# ESP32_AC_dimmer_10ch_r2.net
KiCad netlist of a schematic drawn in EAGLE
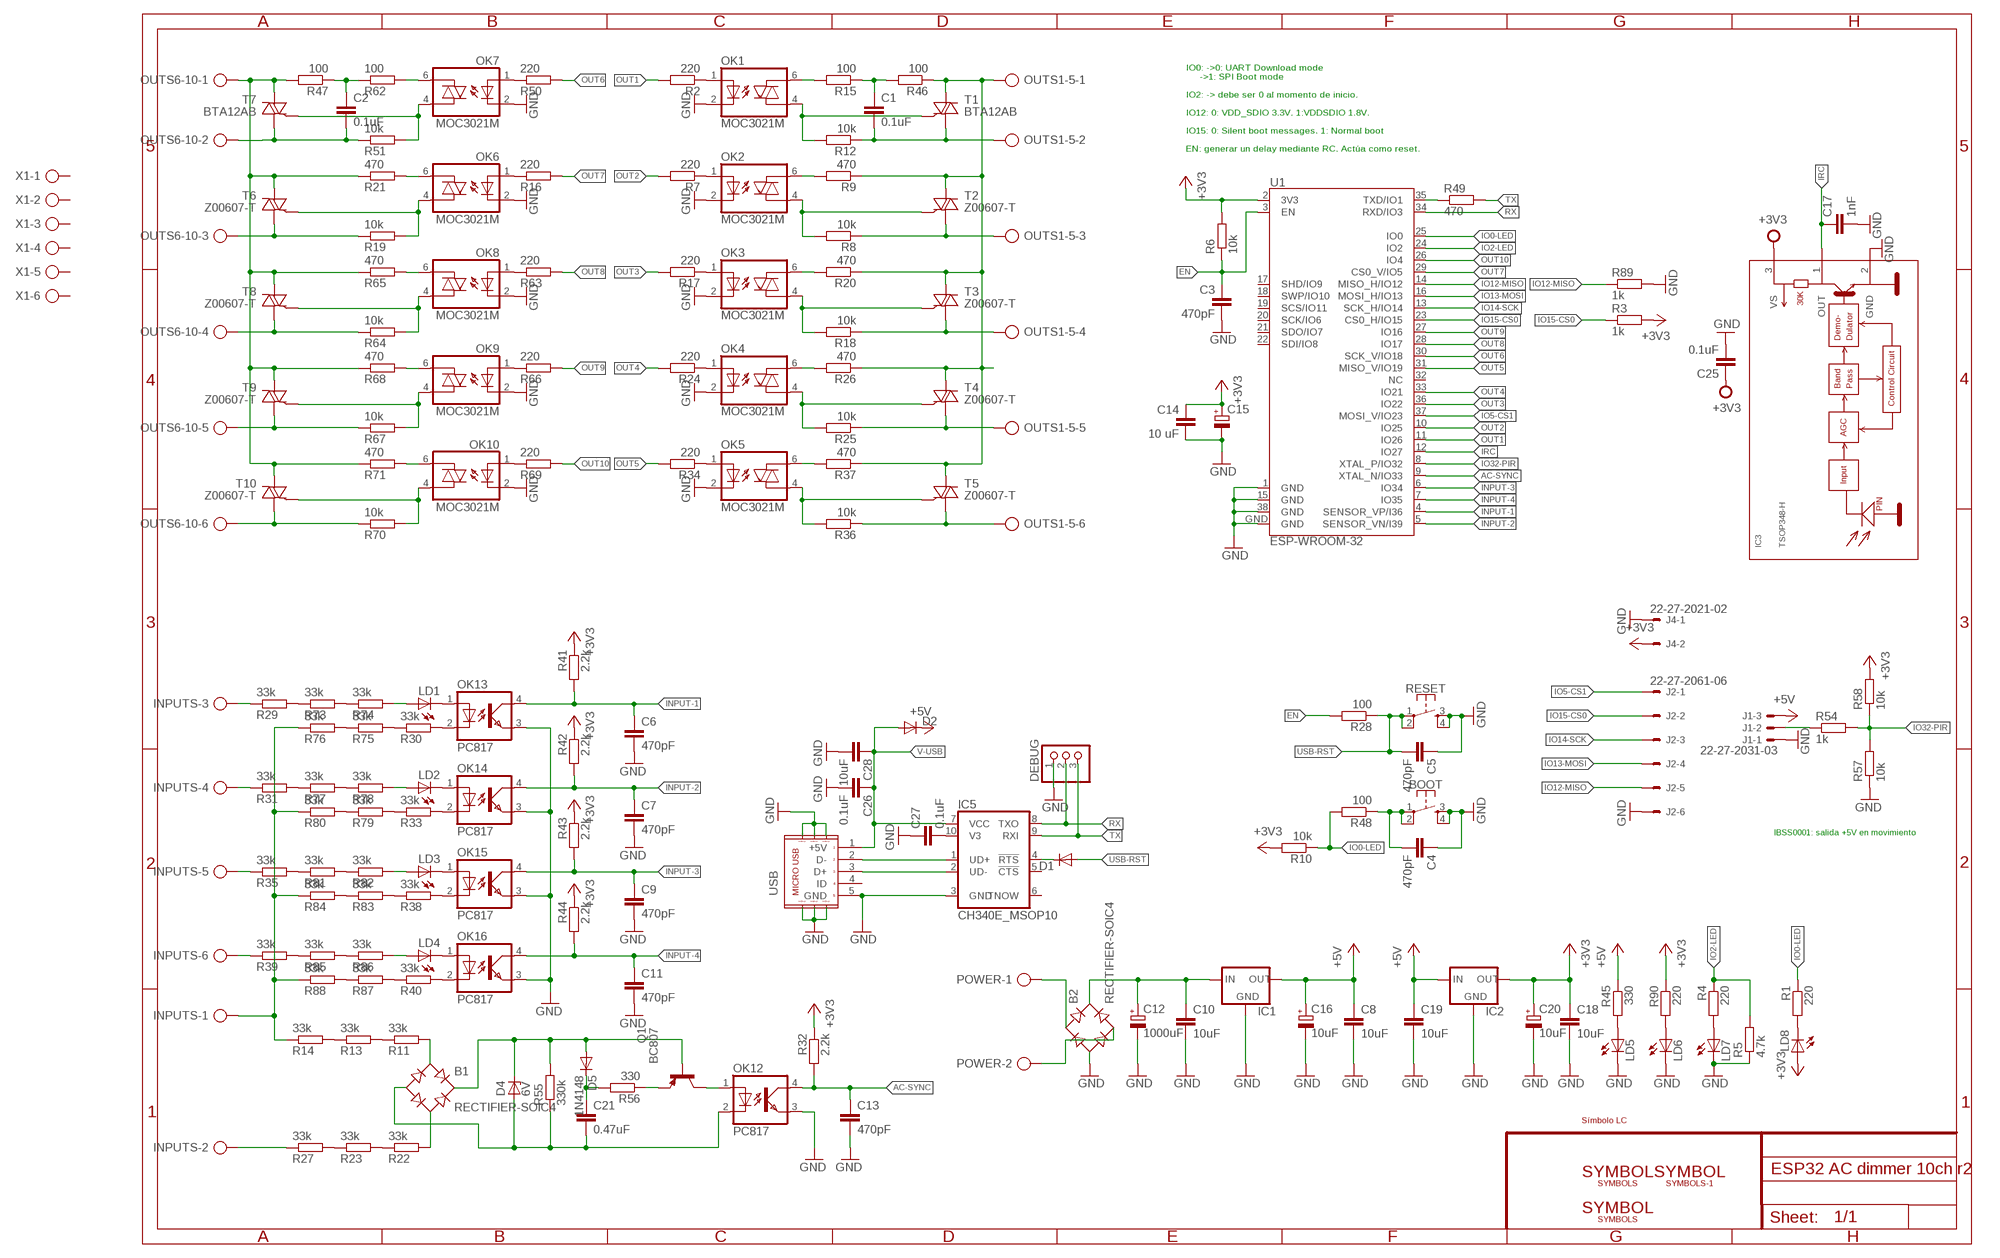
[diagram p0: schematic, sheet 1]

(export (version "E")
  (design (tool "Eeschema 10.0.6"))
  (components
    (comp (ref "B1")
      (value "RECTIFIER-SOIC4")
      (footprint "eagle-import:SOIC4")
      (libsource (lib "eagle-import") (part "RECTIFIER-SOIC4"))
    )
    (comp (ref "B2")
      (value "RECTIFIER-SOIC4")
      (footprint "eagle-import:SOIC4")
      (libsource (lib "eagle-import") (part "RECTIFIER-SOIC4"))
    )
    (comp (ref "BOOT")
      (value "MOMENTARY-SWITCH-SPST-2-SMD-4.6X2.8MM")
      (footprint "eagle-import:TACTILE_SWITCH_SMD_4.6X2.8MM")
      (libsource (lib "eagle-import") (part "MOMENTARY-SWITCH-SPST-2-SMD-4.6X2.8MM"))
    )
    (comp (ref "C1")
      (value "0.1uF")
      (footprint "eagle-import:C075-042X103")
      (libsource (lib "eagle-import") (part "C-EU075-042X103"))
    )
    (comp (ref "C2")
      (value "0.1uF")
      (footprint "eagle-import:C075-042X103")
      (libsource (lib "eagle-import") (part "C-EU075-042X103"))
    )
    (comp (ref "C3")
      (value "470pF")
      (footprint "eagle-import:C0603")
      (libsource (lib "eagle-import") (part "C-EUC0603"))
    )
    (comp (ref "C4")
      (value "470pF")
      (footprint "eagle-import:C0603")
      (libsource (lib "eagle-import") (part "C-EUC0603"))
    )
    (comp (ref "C5")
      (value "470pF")
      (footprint "eagle-import:C0603")
      (libsource (lib "eagle-import") (part "C-EUC0603"))
    )
    (comp (ref "C6")
      (value "470pF")
      (footprint "eagle-import:C0603")
      (libsource (lib "eagle-import") (part "C-EUC0603"))
    )
    (comp (ref "C7")
      (value "470pF")
      (footprint "eagle-import:C0603")
      (libsource (lib "eagle-import") (part "C-EUC0603"))
    )
    (comp (ref "C8")
      (value "10uF")
      (footprint "eagle-import:C0805")
      (libsource (lib "eagle-import") (part "C-EUC0805"))
    )
    (comp (ref "C9")
      (value "470pF")
      (footprint "eagle-import:C0603")
      (libsource (lib "eagle-import") (part "C-EUC0603"))
    )
    (comp (ref "C10")
      (value "10uF")
      (footprint "eagle-import:C0805")
      (libsource (lib "eagle-import") (part "C-EUC0805"))
    )
    (comp (ref "C11")
      (value "470pF")
      (footprint "eagle-import:C0603")
      (libsource (lib "eagle-import") (part "C-EUC0603"))
    )
    (comp (ref "C12")
      (value "1000uF")
      (footprint "eagle-import:E3,5-8")
      (libsource (lib "eagle-import") (part "CPOL-EUE3.5-8"))
    )
    (comp (ref "C13")
      (value "470pF")
      (footprint "eagle-import:C0603")
      (libsource (lib "eagle-import") (part "C-EUC0603"))
    )
    (comp (ref "C14")
      (value "10 uF")
      (footprint "eagle-import:C0805")
      (libsource (lib "eagle-import") (part "C-EUC0805"))
    )
    (comp (ref "C15")
      (value "CPOL-EUSMCA")
      (footprint "eagle-import:SMC_A")
      (libsource (lib "eagle-import") (part "rcl_334_CPOL-EUSMCA"))
    )
    (comp (ref "C16")
      (value "10uF")
      (footprint "eagle-import:SMC_A")
      (libsource (lib "eagle-import") (part "rcl_334_CPOL-EUSMCA"))
    )
    (comp (ref "C17")
      (value "1nF")
      (footprint "eagle-import:C0603")
      (libsource (lib "eagle-import") (part "C-EUC0603"))
    )
    (comp (ref "C18")
      (value "10uF")
      (footprint "eagle-import:C0805")
      (libsource (lib "eagle-import") (part "C-EUC0805"))
    )
    (comp (ref "C19")
      (value "10uF")
      (footprint "eagle-import:C0805")
      (libsource (lib "eagle-import") (part "C-EUC0805"))
    )
    (comp (ref "C20")
      (value "10uF")
      (footprint "eagle-import:SMC_A")
      (libsource (lib "eagle-import") (part "rcl_334_CPOL-EUSMCA"))
    )
    (comp (ref "C21")
      (value "0.47uF")
      (footprint "eagle-import:C0805")
      (libsource (lib "eagle-import") (part "C-EUC0805"))
    )
    (comp (ref "C25")
      (value "0.1uF")
      (footprint "eagle-import:C0603")
      (libsource (lib "eagle-import") (part "C-EUC0603"))
    )
    (comp (ref "C26")
      (value "0.1uF")
      (footprint "eagle-import:C0603")
      (libsource (lib "eagle-import") (part "C-EUC0603"))
    )
    (comp (ref "C27")
      (value "0.1uF")
      (footprint "eagle-import:C0603")
      (libsource (lib "eagle-import") (part "C-EUC0603"))
    )
    (comp (ref "C28")
      (value "10uF")
      (footprint "eagle-import:RCL_C0805")
      (libsource (lib "eagle-import") (part "RCL_C-EUC0805"))
    )
    (comp (ref "D1")
      (value "DIODE-SOD323-R")
      (footprint "eagle-import:SOD323-R")
      (libsource (lib "eagle-import") (part "DIODE-SOD323-R"))
    )
    (comp (ref "D2")
      (value "DIODE-SOD323-R")
      (footprint "eagle-import:SOD323-R")
      (libsource (lib "eagle-import") (part "DIODE-SOD323-R"))
    )
    (comp (ref "D4")
      (value "6V")
      (footprint "eagle-import:SOD80C")
      (libsource (lib "eagle-import") (part "ZENER-DIODESOD80C"))
    )
    (comp (ref "D5")
      (value "1N4148")
      (footprint "eagle-import:MINIMELF")
      (libsource (lib "eagle-import") (part "DIODE-MINIMELF"))
    )
    (comp (ref "DEBUG")
      (value "PINHD-1X3")
      (footprint "eagle-import:1X03")
      (libsource (lib "eagle-import") (part "PINHD-1X3"))
    )
    (comp (ref "IC1")
      (value "LM1117")
      (footprint "eagle-import:SOT223")
      (libsource (lib "eagle-import") (part "LM1117"))
    )
    (comp (ref "IC2")
      (value "LM1117")
      (footprint "eagle-import:SOT223")
      (libsource (lib "eagle-import") (part "LM1117"))
    )
    (comp (ref "IC3")
      (value "TSOP348-H")
      (footprint "eagle-import:TSOP348H")
      (libsource (lib "eagle-import") (part "TSOP348-H"))
    )
    (comp (ref "IC5")
      (value "CH340E_MSOP10")
      (footprint "eagle-import:MSOP10")
      (libsource (lib "eagle-import") (part "CH340E_MSOP10"))
    )
    (comp (ref "INPUTS")
      (value "AK500/6")
      (footprint "eagle-import:AK500_6")
      (libsource (lib "eagle-import") (part "AK500/6"))
    )
    (comp (ref "J1")
      (value "22-27-2031-03")
      (footprint "eagle-import:6410-03")
      (libsource (lib "eagle-import") (part "22-?-0327-2031"))
    )
    (comp (ref "J2")
      (value "22-27-2061-06")
      (footprint "eagle-import:6410-06")
      (fields (field (name "MF") "MOLEX"))
      (libsource (lib "eagle-import") (part "22-?-0627-2061"))
    )
    (comp (ref "J4")
      (value "22-27-2021-02")
      (footprint "eagle-import:6410-02")
      (fields (field (name "MF") "MOLEX"))
      (libsource (lib "eagle-import") (part "22-?-0227-2021"))
    )
    (comp (ref "LD1")
      (value "LEDCHIPLED_0805")
      (footprint "eagle-import:CHIPLED_0805")
      (libsource (lib "eagle-import") (part "LEDCHIPLED_0805"))
    )
    (comp (ref "LD2")
      (value "LEDCHIPLED_0805")
      (footprint "eagle-import:CHIPLED_0805")
      (libsource (lib "eagle-import") (part "LEDCHIPLED_0805"))
    )
    (comp (ref "LD3")
      (value "LEDCHIPLED_0805")
      (footprint "eagle-import:CHIPLED_0805")
      (libsource (lib "eagle-import") (part "LEDCHIPLED_0805"))
    )
    (comp (ref "LD4")
      (value "LEDCHIPLED_0805")
      (footprint "eagle-import:CHIPLED_0805")
      (libsource (lib "eagle-import") (part "LEDCHIPLED_0805"))
    )
    (comp (ref "LD5")
      (value "LEDCHIPLED_0805")
      (footprint "eagle-import:CHIPLED_0805")
      (fields (field (name "SPICEPREFIX") "L"))
      (libsource (lib "eagle-import") (part "LEDCHIPLED_0805"))
    )
    (comp (ref "LD6")
      (value "LEDCHIPLED_0805")
      (footprint "eagle-import:CHIPLED_0805")
      (fields (field (name "SPICEPREFIX") "L"))
      (libsource (lib "eagle-import") (part "LEDCHIPLED_0805"))
    )
    (comp (ref "LD7")
      (value "LEDCHIPLED_0805")
      (footprint "eagle-import:CHIPLED_0805")
      (fields (field (name "SPICEPREFIX") "L"))
      (libsource (lib "eagle-import") (part "LEDCHIPLED_0805"))
    )
    (comp (ref "LD8")
      (value "LEDCHIPLED_0805")
      (footprint "eagle-import:CHIPLED_0805")
      (fields (field (name "SPICEPREFIX") "L"))
      (libsource (lib "eagle-import") (part "LEDCHIPLED_0805"))
    )
    (comp (ref "OK1")
      (value "MOC3021M")
      (footprint "eagle-import:DIL06")
      (libsource (lib "eagle-import") (part "MOC30M21"))
    )
    (comp (ref "OK2")
      (value "MOC3021M")
      (footprint "eagle-import:DIL06")
      (libsource (lib "eagle-import") (part "MOC30M21"))
    )
    (comp (ref "OK3")
      (value "MOC3021M")
      (footprint "eagle-import:DIL06")
      (libsource (lib "eagle-import") (part "MOC30M21"))
    )
    (comp (ref "OK4")
      (value "MOC3021M")
      (footprint "eagle-import:DIL06")
      (libsource (lib "eagle-import") (part "MOC30M21"))
    )
    (comp (ref "OK5")
      (value "MOC3021M")
      (footprint "eagle-import:DIL06")
      (libsource (lib "eagle-import") (part "MOC30M21"))
    )
    (comp (ref "OK6")
      (value "MOC3021M")
      (footprint "eagle-import:DIL06")
      (libsource (lib "eagle-import") (part "MOC30M21"))
    )
    (comp (ref "OK7")
      (value "MOC3021M")
      (footprint "eagle-import:DIL06")
      (libsource (lib "eagle-import") (part "MOC30M21"))
    )
    (comp (ref "OK8")
      (value "MOC3021M")
      (footprint "eagle-import:DIL06")
      (libsource (lib "eagle-import") (part "MOC30M21"))
    )
    (comp (ref "OK9")
      (value "MOC3021M")
      (footprint "eagle-import:DIL06")
      (libsource (lib "eagle-import") (part "MOC30M21"))
    )
    (comp (ref "OK10")
      (value "MOC3021M")
      (footprint "eagle-import:DIL06")
      (libsource (lib "eagle-import") (part "MOC30M21"))
    )
    (comp (ref "OK12")
      (value "PC817")
      (footprint "eagle-import:DIL04")
      (libsource (lib "eagle-import") (part "PC817"))
    )
    (comp (ref "OK13")
      (value "PC817")
      (footprint "eagle-import:DIL04")
      (libsource (lib "eagle-import") (part "PC817"))
    )
    (comp (ref "OK14")
      (value "PC817")
      (footprint "eagle-import:DIL04")
      (libsource (lib "eagle-import") (part "PC817"))
    )
    (comp (ref "OK15")
      (value "PC817")
      (footprint "eagle-import:DIL04")
      (libsource (lib "eagle-import") (part "PC817"))
    )
    (comp (ref "OK16")
      (value "PC817")
      (footprint "eagle-import:DIL04")
      (libsource (lib "eagle-import") (part "PC817"))
    )
    (comp (ref "OUTS1-5")
      (value "AK500/6")
      (footprint "eagle-import:AK500_6")
      (libsource (lib "eagle-import") (part "AK500/6"))
    )
    (comp (ref "OUTS6-10")
      (value "AK500/6")
      (footprint "eagle-import:AK500_6")
      (libsource (lib "eagle-import") (part "AK500/6"))
    )
    (comp (ref "POWER")
      (value "AK500/2")
      (footprint "eagle-import:AK500_2")
      (libsource (lib "eagle-import") (part "AK500/2"))
    )
    (comp (ref "Q1")
      (value "BC807")
      (footprint "eagle-import:SOT23-BEC")
      (libsource (lib "eagle-import") (part "-PNP-SOT23-BECBC807-25"))
    )
    (comp (ref "R1")
      (value "220")
      (footprint "eagle-import:R0603")
      (fields (field (name "SPICEPREFIX") "R"))
      (libsource (lib "eagle-import") (part "R-EU_R0603"))
    )
    (comp (ref "R2")
      (value "220")
      (footprint "eagle-import:R0603")
      (libsource (lib "eagle-import") (part "R-EU_R0603"))
    )
    (comp (ref "R3")
      (value "1k")
      (footprint "eagle-import:R0603")
      (libsource (lib "eagle-import") (part "R-EU_R0603"))
    )
    (comp (ref "R4")
      (value "220")
      (footprint "eagle-import:R0603")
      (fields (field (name "SPICEPREFIX") "R"))
      (libsource (lib "eagle-import") (part "R-EU_R0603"))
    )
    (comp (ref "R5")
      (value "4.7k")
      (footprint "eagle-import:R0603")
      (libsource (lib "eagle-import") (part "R-EU_R0603"))
    )
    (comp (ref "R6")
      (value "10k")
      (footprint "eagle-import:R0603")
      (libsource (lib "eagle-import") (part "R-EU_R0603"))
    )
    (comp (ref "R7")
      (value "220")
      (footprint "eagle-import:R0603")
      (libsource (lib "eagle-import") (part "R-EU_R0603"))
    )
    (comp (ref "R8")
      (value "10k")
      (footprint "eagle-import:0204_5")
      (libsource (lib "eagle-import") (part "R-EU_0204/5"))
    )
    (comp (ref "R9")
      (value "470")
      (footprint "eagle-import:0204_5")
      (libsource (lib "eagle-import") (part "R-EU_0204/5"))
    )
    (comp (ref "R10")
      (value "10k")
      (footprint "eagle-import:R0603")
      (libsource (lib "eagle-import") (part "R-EU_R0603"))
    )
    (comp (ref "R11")
      (value "33k")
      (footprint "eagle-import:R0805")
      (libsource (lib "eagle-import") (part "R-EU_R0805"))
    )
    (comp (ref "R12")
      (value "10k")
      (footprint "eagle-import:0204_5")
      (libsource (lib "eagle-import") (part "R-EU_0204/5"))
    )
    (comp (ref "R13")
      (value "33k")
      (footprint "eagle-import:R0805")
      (libsource (lib "eagle-import") (part "R-EU_R0805"))
    )
    (comp (ref "R14")
      (value "33k")
      (footprint "eagle-import:R0805")
      (libsource (lib "eagle-import") (part "R-EU_R0805"))
    )
    (comp (ref "R15")
      (value "100")
      (footprint "eagle-import:0204_5")
      (libsource (lib "eagle-import") (part "R-EU_0204/5"))
    )
    (comp (ref "R16")
      (value "220")
      (footprint "eagle-import:R0603")
      (libsource (lib "eagle-import") (part "R-EU_R0603"))
    )
    (comp (ref "R17")
      (value "220")
      (footprint "eagle-import:R0603")
      (libsource (lib "eagle-import") (part "R-EU_R0603"))
    )
    (comp (ref "R18")
      (value "10k")
      (footprint "eagle-import:0204_5")
      (libsource (lib "eagle-import") (part "R-EU_0204/5"))
    )
    (comp (ref "R19")
      (value "10k")
      (footprint "eagle-import:0204_5")
      (libsource (lib "eagle-import") (part "R-EU_0204/5"))
    )
    (comp (ref "R20")
      (value "470")
      (footprint "eagle-import:0204_5")
      (libsource (lib "eagle-import") (part "R-EU_0204/5"))
    )
    (comp (ref "R21")
      (value "470")
      (footprint "eagle-import:0204_5")
      (libsource (lib "eagle-import") (part "R-EU_0204/5"))
    )
    (comp (ref "R22")
      (value "33k")
      (footprint "eagle-import:R0805")
      (libsource (lib "eagle-import") (part "R-EU_R0805"))
    )
    (comp (ref "R23")
      (value "33k")
      (footprint "eagle-import:R0805")
      (libsource (lib "eagle-import") (part "R-EU_R0805"))
    )
    (comp (ref "R24")
      (value "220")
      (footprint "eagle-import:R0603")
      (libsource (lib "eagle-import") (part "R-EU_R0603"))
    )
    (comp (ref "R25")
      (value "10k")
      (footprint "eagle-import:0204_5")
      (libsource (lib "eagle-import") (part "R-EU_0204/5"))
    )
    (comp (ref "R26")
      (value "470")
      (footprint "eagle-import:0204_5")
      (libsource (lib "eagle-import") (part "R-EU_0204/5"))
    )
    (comp (ref "R27")
      (value "33k")
      (footprint "eagle-import:R0805")
      (libsource (lib "eagle-import") (part "R-EU_R0805"))
    )
    (comp (ref "R28")
      (value "100")
      (footprint "eagle-import:R0603")
      (libsource (lib "eagle-import") (part "R-EU_R0603"))
    )
    (comp (ref "R29")
      (value "33k")
      (footprint "eagle-import:R0805")
      (libsource (lib "eagle-import") (part "R-EU_R0805"))
    )
    (comp (ref "R30")
      (value "33k")
      (footprint "eagle-import:R0805")
      (libsource (lib "eagle-import") (part "R-EU_R0805"))
    )
    (comp (ref "R31")
      (value "33k")
      (footprint "eagle-import:R0805")
      (libsource (lib "eagle-import") (part "R-EU_R0805"))
    )
    (comp (ref "R32")
      (value "2.2k")
      (footprint "eagle-import:R0603")
      (libsource (lib "eagle-import") (part "R-EU_R0603"))
    )
    (comp (ref "R33")
      (value "33k")
      (footprint "eagle-import:R0805")
      (libsource (lib "eagle-import") (part "R-EU_R0805"))
    )
    (comp (ref "R34")
      (value "220")
      (footprint "eagle-import:R0603")
      (libsource (lib "eagle-import") (part "R-EU_R0603"))
    )
    (comp (ref "R35")
      (value "33k")
      (footprint "eagle-import:R0805")
      (libsource (lib "eagle-import") (part "R-EU_R0805"))
    )
    (comp (ref "R36")
      (value "10k")
      (footprint "eagle-import:0204_5")
      (libsource (lib "eagle-import") (part "R-EU_0204/5"))
    )
    (comp (ref "R37")
      (value "470")
      (footprint "eagle-import:0204_5")
      (libsource (lib "eagle-import") (part "R-EU_0204/5"))
    )
    (comp (ref "R38")
      (value "33k")
      (footprint "eagle-import:R0805")
      (libsource (lib "eagle-import") (part "R-EU_R0805"))
    )
    (comp (ref "R39")
      (value "33k")
      (footprint "eagle-import:R0805")
      (libsource (lib "eagle-import") (part "R-EU_R0805"))
    )
    (comp (ref "R40")
      (value "33k")
      (footprint "eagle-import:R0805")
      (libsource (lib "eagle-import") (part "R-EU_R0805"))
    )
    (comp (ref "R41")
      (value "2.2k")
      (footprint "eagle-import:R0603")
      (libsource (lib "eagle-import") (part "R-EU_R0603"))
    )
    (comp (ref "R42")
      (value "2.2k")
      (footprint "eagle-import:R0603")
      (libsource (lib "eagle-import") (part "R-EU_R0603"))
    )
    (comp (ref "R43")
      (value "2.2k")
      (footprint "eagle-import:R0603")
      (libsource (lib "eagle-import") (part "R-EU_R0603"))
    )
    (comp (ref "R44")
      (value "2.2k")
      (footprint "eagle-import:R0603")
      (libsource (lib "eagle-import") (part "R-EU_R0603"))
    )
    (comp (ref "R45")
      (value "330")
      (footprint "eagle-import:R0603")
      (fields (field (name "SPICEPREFIX") "R"))
      (libsource (lib "eagle-import") (part "R-EU_R0603"))
    )
    (comp (ref "R46")
      (value "100")
      (footprint "eagle-import:0204_7")
      (libsource (lib "eagle-import") (part "R-EU_0204/7"))
    )
    (comp (ref "R47")
      (value "100")
      (footprint "eagle-import:0204_7")
      (libsource (lib "eagle-import") (part "R-EU_0204/7"))
    )
    (comp (ref "R48")
      (value "100")
      (footprint "eagle-import:R0603")
      (libsource (lib "eagle-import") (part "R-EU_R0603"))
    )
    (comp (ref "R49")
      (value "470")
      (footprint "eagle-import:R0603")
      (libsource (lib "eagle-import") (part "R-EU_R0603"))
    )
    (comp (ref "R50")
      (value "220")
      (footprint "eagle-import:R0603")
      (libsource (lib "eagle-import") (part "R-EU_R0603"))
    )
    (comp (ref "R51")
      (value "10k")
      (footprint "eagle-import:0204_5")
      (libsource (lib "eagle-import") (part "R-EU_0204/5"))
    )
    (comp (ref "R54")
      (value "1k")
      (footprint "eagle-import:R0603")
      (libsource (lib "eagle-import") (part "R-EU_R0603"))
    )
    (comp (ref "R55")
      (value "330k")
      (footprint "eagle-import:R0805")
      (libsource (lib "eagle-import") (part "R-EU_R0805"))
    )
    (comp (ref "R56")
      (value "330")
      (footprint "eagle-import:R0805")
      (libsource (lib "eagle-import") (part "R-EU_R0805"))
    )
    (comp (ref "R57")
      (value "10k")
      (footprint "eagle-import:R0603")
      (libsource (lib "eagle-import") (part "R-EU_R0603"))
    )
    (comp (ref "R58")
      (value "10k")
      (footprint "eagle-import:R0603")
      (libsource (lib "eagle-import") (part "R-EU_R0603"))
    )
    (comp (ref "R62")
      (value "100")
      (footprint "eagle-import:0204_5")
      (libsource (lib "eagle-import") (part "R-EU_0204/5"))
    )
    (comp (ref "R63")
      (value "220")
      (footprint "eagle-import:R0603")
      (libsource (lib "eagle-import") (part "R-EU_R0603"))
    )
    (comp (ref "R64")
      (value "10k")
      (footprint "eagle-import:0204_5")
      (libsource (lib "eagle-import") (part "R-EU_0204/5"))
    )
    (comp (ref "R65")
      (value "470")
      (footprint "eagle-import:0204_5")
      (libsource (lib "eagle-import") (part "R-EU_0204/5"))
    )
    (comp (ref "R66")
      (value "220")
      (footprint "eagle-import:R0603")
      (libsource (lib "eagle-import") (part "R-EU_R0603"))
    )
    (comp (ref "R67")
      (value "10k")
      (footprint "eagle-import:0204_5")
      (libsource (lib "eagle-import") (part "R-EU_0204/5"))
    )
    (comp (ref "R68")
      (value "470")
      (footprint "eagle-import:0204_5")
      (libsource (lib "eagle-import") (part "R-EU_0204/5"))
    )
    (comp (ref "R69")
      (value "220")
      (footprint "eagle-import:R0603")
      (libsource (lib "eagle-import") (part "R-EU_R0603"))
    )
    (comp (ref "R70")
      (value "10k")
      (footprint "eagle-import:0204_5")
      (libsource (lib "eagle-import") (part "R-EU_0204/5"))
    )
    (comp (ref "R71")
      (value "470")
      (footprint "eagle-import:0204_5")
      (libsource (lib "eagle-import") (part "R-EU_0204/5"))
    )
    (comp (ref "R73")
      (value "33k")
      (footprint "eagle-import:R0805")
      (libsource (lib "eagle-import") (part "R-EU_R0805"))
    )
    (comp (ref "R74")
      (value "33k")
      (footprint "eagle-import:R0805")
      (libsource (lib "eagle-import") (part "R-EU_R0805"))
    )
    (comp (ref "R75")
      (value "33k")
      (footprint "eagle-import:R0805")
      (libsource (lib "eagle-import") (part "R-EU_R0805"))
    )
    (comp (ref "R76")
      (value "33k")
      (footprint "eagle-import:R0805")
      (libsource (lib "eagle-import") (part "R-EU_R0805"))
    )
    (comp (ref "R77")
      (value "33k")
      (footprint "eagle-import:R0805")
      (libsource (lib "eagle-import") (part "R-EU_R0805"))
    )
    (comp (ref "R78")
      (value "33k")
      (footprint "eagle-import:R0805")
      (libsource (lib "eagle-import") (part "R-EU_R0805"))
    )
    (comp (ref "R79")
      (value "33k")
      (footprint "eagle-import:R0805")
      (libsource (lib "eagle-import") (part "R-EU_R0805"))
    )
    (comp (ref "R80")
      (value "33k")
      (footprint "eagle-import:R0805")
      (libsource (lib "eagle-import") (part "R-EU_R0805"))
    )
    (comp (ref "R81")
      (value "33k")
      (footprint "eagle-import:R0805")
      (libsource (lib "eagle-import") (part "R-EU_R0805"))
    )
    (comp (ref "R82")
      (value "33k")
      (footprint "eagle-import:R0805")
      (libsource (lib "eagle-import") (part "R-EU_R0805"))
    )
    (comp (ref "R83")
      (value "33k")
      (footprint "eagle-import:R0805")
      (libsource (lib "eagle-import") (part "R-EU_R0805"))
    )
    (comp (ref "R84")
      (value "33k")
      (footprint "eagle-import:R0805")
      (libsource (lib "eagle-import") (part "R-EU_R0805"))
    )
    (comp (ref "R85")
      (value "33k")
      (footprint "eagle-import:R0805")
      (libsource (lib "eagle-import") (part "R-EU_R0805"))
    )
    (comp (ref "R86")
      (value "33k")
      (footprint "eagle-import:R0805")
      (libsource (lib "eagle-import") (part "R-EU_R0805"))
    )
    (comp (ref "R87")
      (value "33k")
      (footprint "eagle-import:R0805")
      (libsource (lib "eagle-import") (part "R-EU_R0805"))
    )
    (comp (ref "R88")
      (value "33k")
      (footprint "eagle-import:R0805")
      (libsource (lib "eagle-import") (part "R-EU_R0805"))
    )
    (comp (ref "R89")
      (value "1k")
      (footprint "eagle-import:R0603")
      (libsource (lib "eagle-import") (part "R-EU_R0603"))
    )
    (comp (ref "R90")
      (value "220")
      (footprint "eagle-import:R0603")
      (fields (field (name "SPICEPREFIX") "R"))
      (libsource (lib "eagle-import") (part "R-EU_R0603"))
    )
    (comp (ref "RESET")
      (value "MOMENTARY-SWITCH-SPST-2-SMD-4.6X2.8MM")
      (footprint "eagle-import:TACTILE_SWITCH_SMD_4.6X2.8MM")
      (libsource (lib "eagle-import") (part "MOMENTARY-SWITCH-SPST-2-SMD-4.6X2.8MM"))
    )
    (comp (ref "SYM1")
      (value "LC-3.81")
      (footprint "eagle-import:LC_3.81MM")
      (libsource (lib "eagle-import") (part "LC-3.81"))
    )
    (comp (ref "T1")
      (value "BTA12AB")
      (footprint "eagle-import:TO220DS")
      (libsource (lib "eagle-import") (part "BTA12AB"))
    )
    (comp (ref "T2")
      (value "Z00607-T")
      (footprint "eagle-import:TO92-A1GA2")
      (libsource (lib "eagle-import") (part "Z00607-T"))
    )
    (comp (ref "T3")
      (value "Z00607-T")
      (footprint "eagle-import:TO92-A1GA2")
      (libsource (lib "eagle-import") (part "Z00607-T"))
    )
    (comp (ref "T4")
      (value "Z00607-T")
      (footprint "eagle-import:TO92-A1GA2")
      (libsource (lib "eagle-import") (part "Z00607-T"))
    )
    (comp (ref "T5")
      (value "Z00607-T")
      (footprint "eagle-import:TO92-A1GA2")
      (libsource (lib "eagle-import") (part "Z00607-T"))
    )
    (comp (ref "T6")
      (value "Z00607-T")
      (footprint "eagle-import:TO92-A1GA2")
      (libsource (lib "eagle-import") (part "Z00607-T"))
    )
    (comp (ref "T7")
      (value "BTA12AB")
      (footprint "eagle-import:TO220DS")
      (libsource (lib "eagle-import") (part "BTA12AB"))
    )
    (comp (ref "T8")
      (value "Z00607-T")
      (footprint "eagle-import:TO92-A1GA2")
      (libsource (lib "eagle-import") (part "Z00607-T"))
    )
    (comp (ref "T9")
      (value "Z00607-T")
      (footprint "eagle-import:TO92-A1GA2")
      (libsource (lib "eagle-import") (part "Z00607-T"))
    )
    (comp (ref "T10")
      (value "Z00607-T")
      (footprint "eagle-import:TO92-A1GA2")
      (libsource (lib "eagle-import") (part "Z00607-T"))
    )
    (comp (ref "U$1")
      (value "SYMBOLS")
      (footprint "eagle-import:WIFI_SYM")
      (libsource (lib "eagle-import") (part "SYMBOLS"))
    )
    (comp (ref "U$2")
      (value "SYMBOLS")
      (footprint "eagle-import:WIFI_SYM")
      (libsource (lib "eagle-import") (part "SYMBOLS"))
    )
    (comp (ref "U$3")
      (value "SYMBOLS-1")
      (footprint "eagle-import:WIFI-SYM2")
      (libsource (lib "eagle-import") (part "SYMBOLS-1"))
    )
    (comp (ref "U1")
      (value "ESP-WROOM-32")
      (footprint "eagle-import:ESP-WROOM-32")
      (libsource (lib "eagle-import") (part "ESP-WROOM-32"))
    )
    (comp (ref "USB")
      (value "MICROUSB-LP")
      (footprint "eagle-import:MICROUSB-4PIN-LONGPIN")
      (libsource (lib "eagle-import") (part "MICROUSB-LP"))
    )
    (comp (ref "X1")
      (value "AK300/6")
      (footprint "eagle-import:AK300_6")
      (libsource (lib "eagle-import") (part "AK300/6"))
    )
  )
  (nets
    (net (code "1") (name "+3V3") (class "Default")
      (node (ref "C14") (pin "1") (pinfunction "1_1") (pintype "passive"))
      (node (ref "C15") (pin "+") (pinfunction "+_+") (pintype "passive"))
      (node (ref "C18") (pin "1") (pinfunction "1_1") (pintype "passive"))
      (node (ref "C20") (pin "+") (pinfunction "+_+") (pintype "passive"))
      (node (ref "C25") (pin "1") (pinfunction "1_1") (pintype "passive"))
      (node (ref "IC2") (pin "2") (pinfunction "OUT_2") (pintype "passive"))
      (node (ref "IC3") (pin "3") (pinfunction "VS_3") (pintype "power_in"))
      (node (ref "J4") (pin "2") (pinfunction "S_2") (pintype "passive"))
      (node (ref "LD8") (pin "A") (pinfunction "A_A") (pintype "passive"))
      (node (ref "R10") (pin "2") (pinfunction "2_2") (pintype "passive"))
      (node (ref "R3") (pin "2") (pinfunction "2_2") (pintype "passive"))
      (node (ref "R32") (pin "1") (pinfunction "1_1") (pintype "passive"))
      (node (ref "R41") (pin "1") (pinfunction "1_1") (pintype "passive"))
      (node (ref "R42") (pin "1") (pinfunction "1_1") (pintype "passive"))
      (node (ref "R43") (pin "1") (pinfunction "1_1") (pintype "passive"))
      (node (ref "R44") (pin "1") (pinfunction "1_1") (pintype "passive"))
      (node (ref "R58") (pin "2") (pinfunction "2_2") (pintype "passive"))
      (node (ref "R6") (pin "2") (pinfunction "2_2") (pintype "passive"))
      (node (ref "R90") (pin "1") (pinfunction "1_1") (pintype "passive"))
      (node (ref "U1") (pin "2") (pinfunction "3V3_2") (pintype "bidirectional"))
    )
    (net (code "2") (name "+5V") (class "Default")
      (node (ref "C16") (pin "+") (pinfunction "+_+") (pintype "passive"))
      (node (ref "C19") (pin "1") (pinfunction "1_1") (pintype "passive"))
      (node (ref "C8") (pin "1") (pinfunction "1_1") (pintype "passive"))
      (node (ref "D2") (pin "C") (pinfunction "C_C") (pintype "passive"))
      (node (ref "IC1") (pin "2") (pinfunction "OUT_2") (pintype "passive"))
      (node (ref "IC2") (pin "3") (pinfunction "IN_3") (pintype "input"))
      (node (ref "J1") (pin "3") (pinfunction "S_3") (pintype "passive"))
      (node (ref "R45") (pin "1") (pinfunction "1_1") (pintype "passive"))
    )
    (net (code "3") (name "AC-SYNC") (class "Default")
      (node (ref "C13") (pin "1") (pinfunction "1_1") (pintype "passive"))
      (node (ref "OK12") (pin "4") (pinfunction "COL_4") (pintype "passive"))
      (node (ref "R32") (pin "2") (pinfunction "2_2") (pintype "passive"))
      (node (ref "U1") (pin "9") (pinfunction "XTAL_N/IO33_9") (pintype "bidirectional"))
    )
    (net (code "4") (name "EN") (class "Default")
      (node (ref "C3") (pin "1") (pinfunction "1_1") (pintype "passive"))
      (node (ref "R28") (pin "2") (pinfunction "2_2") (pintype "passive"))
      (node (ref "R6") (pin "1") (pinfunction "1_1") (pintype "passive"))
      (node (ref "U1") (pin "3") (pinfunction "EN_3") (pintype "bidirectional"))
    )
    (net (code "5") (name "GND") (class "Default")
      (node (ref "B2") (pin "-") (pinfunction "-_-") (pintype "passive"))
      (node (ref "BOOT") (pin "3") (pinfunction "3_3") (pintype "passive"))
      (node (ref "BOOT") (pin "4") (pinfunction "4_4") (pintype "passive"))
      (node (ref "C10") (pin "2") (pinfunction "2_2") (pintype "passive"))
      (node (ref "C11") (pin "2") (pinfunction "2_2") (pintype "passive"))
      (node (ref "C12") (pin "-") (pinfunction "-_-") (pintype "passive"))
      (node (ref "C13") (pin "2") (pinfunction "2_2") (pintype "passive"))
      (node (ref "C14") (pin "2") (pinfunction "2_2") (pintype "passive"))
      (node (ref "C15") (pin "-") (pinfunction "-_-") (pintype "passive"))
      (node (ref "C16") (pin "-") (pinfunction "-_-") (pintype "passive"))
      (node (ref "C17") (pin "2") (pinfunction "2_2") (pintype "passive"))
      (node (ref "C18") (pin "2") (pinfunction "2_2") (pintype "passive"))
      (node (ref "C19") (pin "2") (pinfunction "2_2") (pintype "passive"))
      (node (ref "C20") (pin "-") (pinfunction "-_-") (pintype "passive"))
      (node (ref "C25") (pin "2") (pinfunction "2_2") (pintype "passive"))
      (node (ref "C26") (pin "2") (pinfunction "2_2") (pintype "passive"))
      (node (ref "C27") (pin "1") (pinfunction "1_1") (pintype "passive"))
      (node (ref "C28") (pin "2") (pinfunction "2_2") (pintype "passive"))
      (node (ref "C3") (pin "2") (pinfunction "2_2") (pintype "passive"))
      (node (ref "C4") (pin "1") (pinfunction "1_1") (pintype "passive"))
      (node (ref "C5") (pin "1") (pinfunction "1_1") (pintype "passive"))
      (node (ref "C6") (pin "2") (pinfunction "2_2") (pintype "passive"))
      (node (ref "C7") (pin "2") (pinfunction "2_2") (pintype "passive"))
      (node (ref "C8") (pin "2") (pinfunction "2_2") (pintype "passive"))
      (node (ref "C9") (pin "2") (pinfunction "2_2") (pintype "passive"))
      (node (ref "DEBUG") (pin "1") (pinfunction "1_1") (pintype "passive"))
      (node (ref "IC1") (pin "1") (pinfunction "GND_1") (pintype "input"))
      (node (ref "IC2") (pin "1") (pinfunction "GND_1") (pintype "input"))
      (node (ref "IC3") (pin "2") (pinfunction "GND_2") (pintype "power_in"))
      (node (ref "IC5") (pin "3") (pinfunction "GND_3") (pintype "bidirectional"))
      (node (ref "J1") (pin "1") (pinfunction "S_1") (pintype "passive"))
      (node (ref "J2") (pin "6") (pinfunction "S_6") (pintype "passive"))
      (node (ref "J4") (pin "1") (pinfunction "S_1") (pintype "passive"))
      (node (ref "LD5") (pin "C") (pinfunction "C_C") (pintype "passive"))
      (node (ref "LD6") (pin "C") (pinfunction "C_C") (pintype "passive"))
      (node (ref "LD7") (pin "C") (pinfunction "C_C") (pintype "passive"))
      (node (ref "OK1") (pin "2") (pinfunction "C_2") (pintype "passive"))
      (node (ref "OK10") (pin "2") (pinfunction "C_2") (pintype "passive"))
      (node (ref "OK12") (pin "3") (pinfunction "EMIT_3") (pintype "passive"))
      (node (ref "OK13") (pin "3") (pinfunction "EMIT_3") (pintype "passive"))
      (node (ref "OK14") (pin "3") (pinfunction "EMIT_3") (pintype "passive"))
      (node (ref "OK15") (pin "3") (pinfunction "EMIT_3") (pintype "passive"))
      (node (ref "OK16") (pin "3") (pinfunction "EMIT_3") (pintype "passive"))
      (node (ref "OK2") (pin "2") (pinfunction "C_2") (pintype "passive"))
      (node (ref "OK3") (pin "2") (pinfunction "C_2") (pintype "passive"))
      (node (ref "OK4") (pin "2") (pinfunction "C_2") (pintype "passive"))
      (node (ref "OK5") (pin "2") (pinfunction "C_2") (pintype "passive"))
      (node (ref "OK6") (pin "2") (pinfunction "C_2") (pintype "passive"))
      (node (ref "OK7") (pin "2") (pinfunction "C_2") (pintype "passive"))
      (node (ref "OK8") (pin "2") (pinfunction "C_2") (pintype "passive"))
      (node (ref "OK9") (pin "2") (pinfunction "C_2") (pintype "passive"))
      (node (ref "R5") (pin "1") (pinfunction "1_1") (pintype "passive"))
      (node (ref "R57") (pin "1") (pinfunction "1_1") (pintype "passive"))
      (node (ref "R89") (pin "2") (pinfunction "2_2") (pintype "passive"))
      (node (ref "RESET") (pin "3") (pinfunction "3_3") (pintype "passive"))
      (node (ref "RESET") (pin "4") (pinfunction "4_4") (pintype "passive"))
      (node (ref "U1") (pin "1") (pinfunction "GND_1") (pintype "bidirectional"))
      (node (ref "U1") (pin "15") (pinfunction "GND_15") (pintype "bidirectional"))
      (node (ref "U1") (pin "38") (pinfunction "GND_38") (pintype "bidirectional"))
      (node (ref "U1") (pin "GND") (pinfunction "GND_GND") (pintype "bidirectional"))
      (node (ref "USB") (pin "5") (pinfunction "GND_5") (pintype "bidirectional"))
      (node (ref "USB") (pin "P1") (pinfunction "P1_P1") (pintype "bidirectional"))
      (node (ref "USB") (pin "P2") (pinfunction "P2_P2") (pintype "bidirectional"))
      (node (ref "USB") (pin "P3") (pinfunction "P3_P3") (pintype "bidirectional"))
      (node (ref "USB") (pin "P4") (pinfunction "P4_P4") (pintype "bidirectional"))
      (node (ref "USB") (pin "P5") (pinfunction "P5_P5") (pintype "bidirectional"))
      (node (ref "USB") (pin "P6") (pinfunction "P6_P6") (pintype "bidirectional"))
    )
    (net (code "6") (name "INPUT-1") (class "Default")
      (node (ref "C6") (pin "1") (pinfunction "1_1") (pintype "passive"))
      (node (ref "OK13") (pin "4") (pinfunction "COL_4") (pintype "passive"))
      (node (ref "R41") (pin "2") (pinfunction "2_2") (pintype "passive"))
      (node (ref "U1") (pin "4") (pinfunction "SENSOR_VP/I36_4") (pintype "bidirectional"))
    )
    (net (code "7") (name "INPUT-2") (class "Default")
      (node (ref "C7") (pin "1") (pinfunction "1_1") (pintype "passive"))
      (node (ref "OK14") (pin "4") (pinfunction "COL_4") (pintype "passive"))
      (node (ref "R42") (pin "2") (pinfunction "2_2") (pintype "passive"))
      (node (ref "U1") (pin "5") (pinfunction "SENSOR_VN/I39_5") (pintype "bidirectional"))
    )
    (net (code "8") (name "INPUT-3") (class "Default")
      (node (ref "C9") (pin "1") (pinfunction "1_1") (pintype "passive"))
      (node (ref "OK15") (pin "4") (pinfunction "COL_4") (pintype "passive"))
      (node (ref "R43") (pin "2") (pinfunction "2_2") (pintype "passive"))
      (node (ref "U1") (pin "6") (pinfunction "IO34_6") (pintype "bidirectional"))
    )
    (net (code "9") (name "INPUT-4") (class "Default")
      (node (ref "C11") (pin "1") (pinfunction "1_1") (pintype "passive"))
      (node (ref "OK16") (pin "4") (pinfunction "COL_4") (pintype "passive"))
      (node (ref "R44") (pin "2") (pinfunction "2_2") (pintype "passive"))
      (node (ref "U1") (pin "7") (pinfunction "IO35_7") (pintype "bidirectional"))
    )
    (net (code "10") (name "IO0-LED") (class "Default")
      (node (ref "R1") (pin "1") (pinfunction "1_1") (pintype "passive"))
      (node (ref "R10") (pin "1") (pinfunction "1_1") (pintype "passive"))
      (node (ref "R48") (pin "2") (pinfunction "2_2") (pintype "passive"))
      (node (ref "U1") (pin "25") (pinfunction "IO0_25") (pintype "bidirectional"))
    )
    (net (code "11") (name "IO2-LED") (class "Default")
      (node (ref "R4") (pin "1") (pinfunction "1_1") (pintype "passive"))
      (node (ref "R5") (pin "2") (pinfunction "2_2") (pintype "passive"))
      (node (ref "U1") (pin "24") (pinfunction "IO2_24") (pintype "bidirectional"))
    )
    (net (code "12") (name "IO5-CS1") (class "Default")
      (node (ref "J2") (pin "1") (pinfunction "S_1") (pintype "passive"))
      (node (ref "U1") (pin "37") (pinfunction "MOSI_V/IO23_37") (pintype "bidirectional"))
    )
    (net (code "13") (name "IO12-MISO") (class "Default")
      (node (ref "J2") (pin "5") (pinfunction "S_5") (pintype "passive"))
      (node (ref "R89") (pin "1") (pinfunction "1_1") (pintype "passive"))
      (node (ref "U1") (pin "14") (pinfunction "MISO_H/IO12_14") (pintype "bidirectional"))
    )
    (net (code "14") (name "IO13-MOSI") (class "Default")
      (node (ref "J2") (pin "4") (pinfunction "S_4") (pintype "passive"))
      (node (ref "U1") (pin "16") (pinfunction "MOSI_H/IO13_16") (pintype "bidirectional"))
    )
    (net (code "15") (name "IO14-SCK") (class "Default")
      (node (ref "J2") (pin "3") (pinfunction "S_3") (pintype "passive"))
      (node (ref "U1") (pin "13") (pinfunction "SCK_H/IO14_13") (pintype "bidirectional"))
    )
    (net (code "16") (name "IO15-CS0") (class "Default")
      (node (ref "J2") (pin "2") (pinfunction "S_2") (pintype "passive"))
      (node (ref "R3") (pin "1") (pinfunction "1_1") (pintype "passive"))
      (node (ref "U1") (pin "23") (pinfunction "CS0_H/IO15_23") (pintype "bidirectional"))
    )
    (net (code "17") (name "IO32-PIR") (class "Default")
      (node (ref "R54") (pin "2") (pinfunction "2_2") (pintype "passive"))
      (node (ref "R57") (pin "2") (pinfunction "2_2") (pintype "passive"))
      (node (ref "R58") (pin "1") (pinfunction "1_1") (pintype "passive"))
      (node (ref "U1") (pin "8") (pinfunction "XTAL_P/IO32_8") (pintype "bidirectional"))
    )
    (net (code "18") (name "IRC") (class "Default")
      (node (ref "C17") (pin "1") (pinfunction "1_1") (pintype "passive"))
      (node (ref "IC3") (pin "1") (pinfunction "OUT_1") (pintype "output"))
      (node (ref "U1") (pin "12") (pinfunction "IO27_12") (pintype "bidirectional"))
    )
    (net (code "19") (name "Net-(B1-Pad+)") (class "Default")
      (node (ref "B1") (pin "+") (pinfunction "+_+") (pintype "passive"))
      (node (ref "D4") (pin "C") (pinfunction "C_C") (pintype "passive"))
      (node (ref "D5") (pin "A") (pinfunction "A_A") (pintype "passive"))
      (node (ref "Q1") (pin "B") (pinfunction "B_B") (pintype "passive"))
      (node (ref "R55") (pin "2") (pinfunction "2_2") (pintype "passive"))
    )
    (net (code "20") (name "Net-(B1-PadAC1)") (class "Default")
      (node (ref "B1") (pin "AC1") (pinfunction "AC1_AC1") (pintype "passive"))
      (node (ref "R11") (pin "2") (pinfunction "2_2") (pintype "passive"))
    )
    (net (code "21") (name "Net-(B1-PadAC2)") (class "Default")
      (node (ref "B1") (pin "AC2") (pinfunction "AC2_AC2") (pintype "passive"))
      (node (ref "R22") (pin "2") (pinfunction "2_2") (pintype "passive"))
    )
    (net (code "22") (name "Net-(BOOT-Pad1)") (class "Default")
      (node (ref "BOOT") (pin "1") (pinfunction "1_1") (pintype "passive"))
      (node (ref "BOOT") (pin "2") (pinfunction "2_2") (pintype "passive"))
      (node (ref "C4") (pin "2") (pinfunction "2_2") (pintype "passive"))
      (node (ref "R48") (pin "1") (pinfunction "1_1") (pintype "passive"))
    )
    (net (code "23") (name "Net-(C1-Pad1)") (class "Default")
      (node (ref "C1") (pin "1") (pinfunction "1_1") (pintype "passive"))
      (node (ref "R15") (pin "1") (pinfunction "1_1") (pintype "passive"))
      (node (ref "R46") (pin "2") (pinfunction "2_2") (pintype "passive"))
    )
    (net (code "24") (name "Net-(C2-Pad1)") (class "Default")
      (node (ref "C2") (pin "1") (pinfunction "1_1") (pintype "passive"))
      (node (ref "R47") (pin "1") (pinfunction "1_1") (pintype "passive"))
      (node (ref "R62") (pin "1") (pinfunction "1_1") (pintype "passive"))
    )
    (net (code "25") (name "Net-(C21-Pad1)") (class "Default")
      (node (ref "C21") (pin "1") (pinfunction "1_1") (pintype "passive"))
      (node (ref "D5") (pin "C") (pinfunction "C_C") (pintype "passive"))
      (node (ref "R56") (pin "2") (pinfunction "2_2") (pintype "passive"))
    )
    (net (code "26") (name "Net-(IC1-IN)") (class "Default")
      (node (ref "B2") (pin "+") (pinfunction "+_+") (pintype "passive"))
      (node (ref "C10") (pin "1") (pinfunction "1_1") (pintype "passive"))
      (node (ref "C12") (pin "+") (pinfunction "+_+") (pintype "passive"))
      (node (ref "IC1") (pin "3") (pinfunction "IN_3") (pintype "input"))
    )
    (net (code "27") (name "Net-(IC5-UD+)") (class "Default")
      (node (ref "IC5") (pin "1") (pinfunction "UD+_1") (pintype "bidirectional"))
      (node (ref "USB") (pin "2") (pinfunction "D-_2") (pintype "bidirectional"))
    )
    (net (code "28") (name "Net-(IC5-UD-)") (class "Default")
      (node (ref "IC5") (pin "2") (pinfunction "UD-_2") (pintype "bidirectional"))
      (node (ref "USB") (pin "3") (pinfunction "D+_3") (pintype "bidirectional"))
    )
    (net (code "29") (name "Net-(IC5-V3)") (class "Default")
      (node (ref "C27") (pin "2") (pinfunction "2_2") (pintype "passive"))
      (node (ref "IC5") (pin "10") (pinfunction "V3_10") (pintype "bidirectional"))
    )
    (net (code "30") (name "Net-(IC5-~{RTS})") (class "Default")
      (node (ref "D1") (pin "C") (pinfunction "C_C") (pintype "passive"))
      (node (ref "IC5") (pin "4") (pinfunction "~{RTS}_4") (pintype "bidirectional"))
    )
    (net (code "31") (name "Net-(INPUTSA-KL)") (class "Default")
      (node (ref "INPUTS") (pin "1") (pinfunction "KL_1") (pintype "passive"))
      (node (ref "R14") (pin "1") (pinfunction "1_1") (pintype "passive"))
      (node (ref "R76") (pin "1") (pinfunction "1_1") (pintype "passive"))
      (node (ref "R80") (pin "1") (pinfunction "1_1") (pintype "passive"))
      (node (ref "R84") (pin "1") (pinfunction "1_1") (pintype "passive"))
      (node (ref "R88") (pin "1") (pinfunction "1_1") (pintype "passive"))
    )
    (net (code "32") (name "Net-(INPUTSB-KL)") (class "Default")
      (node (ref "INPUTS") (pin "2") (pinfunction "KL_2") (pintype "passive"))
      (node (ref "R27") (pin "1") (pinfunction "1_1") (pintype "passive"))
    )
    (net (code "33") (name "Net-(INPUTSC-KL)") (class "Default")
      (node (ref "INPUTS") (pin "3") (pinfunction "KL_3") (pintype "passive"))
      (node (ref "R29") (pin "1") (pinfunction "1_1") (pintype "passive"))
    )
    (net (code "34") (name "Net-(INPUTSD-KL)") (class "Default")
      (node (ref "INPUTS") (pin "4") (pinfunction "KL_4") (pintype "passive"))
      (node (ref "R31") (pin "1") (pinfunction "1_1") (pintype "passive"))
    )
    (net (code "35") (name "Net-(INPUTSE-KL)") (class "Default")
      (node (ref "INPUTS") (pin "5") (pinfunction "KL_5") (pintype "passive"))
      (node (ref "R35") (pin "1") (pinfunction "1_1") (pintype "passive"))
    )
    (net (code "36") (name "Net-(INPUTSF-KL)") (class "Default")
      (node (ref "INPUTS") (pin "6") (pinfunction "KL_6") (pintype "passive"))
      (node (ref "R39") (pin "1") (pinfunction "1_1") (pintype "passive"))
    )
    (net (code "37") (name "Net-(J1B-S)") (class "Default")
      (node (ref "J1") (pin "2") (pinfunction "S_2") (pintype "passive"))
      (node (ref "R54") (pin "1") (pinfunction "1_1") (pintype "passive"))
    )
    (net (code "38") (name "Net-(LD1-PadA)") (class "Default")
      (node (ref "LD1") (pin "A") (pinfunction "A_A") (pintype "passive"))
      (node (ref "R74") (pin "2") (pinfunction "2_2") (pintype "passive"))
    )
    (net (code "39") (name "Net-(LD2-PadA)") (class "Default")
      (node (ref "LD2") (pin "A") (pinfunction "A_A") (pintype "passive"))
      (node (ref "R78") (pin "2") (pinfunction "2_2") (pintype "passive"))
    )
    (net (code "40") (name "Net-(LD3-PadA)") (class "Default")
      (node (ref "LD3") (pin "A") (pinfunction "A_A") (pintype "passive"))
      (node (ref "R82") (pin "2") (pinfunction "2_2") (pintype "passive"))
    )
    (net (code "41") (name "Net-(LD4-PadA)") (class "Default")
      (node (ref "LD4") (pin "A") (pinfunction "A_A") (pintype "passive"))
      (node (ref "R86") (pin "2") (pinfunction "2_2") (pintype "passive"))
    )
    (net (code "42") (name "Net-(LD5-PadA)") (class "Default")
      (node (ref "LD5") (pin "A") (pinfunction "A_A") (pintype "passive"))
      (node (ref "R45") (pin "2") (pinfunction "2_2") (pintype "passive"))
    )
    (net (code "43") (name "Net-(LD6-PadA)") (class "Default")
      (node (ref "LD6") (pin "A") (pinfunction "A_A") (pintype "passive"))
      (node (ref "R90") (pin "2") (pinfunction "2_2") (pintype "passive"))
    )
    (net (code "44") (name "Net-(LD7-PadA)") (class "Default")
      (node (ref "LD7") (pin "A") (pinfunction "A_A") (pintype "passive"))
      (node (ref "R4") (pin "2") (pinfunction "2_2") (pintype "passive"))
    )
    (net (code "45") (name "Net-(LD8-PadC)") (class "Default")
      (node (ref "LD8") (pin "C") (pinfunction "C_C") (pintype "passive"))
      (node (ref "R1") (pin "2") (pinfunction "2_2") (pintype "passive"))
    )
    (net (code "46") (name "Net-(OK1-A)") (class "Default")
      (node (ref "OK1") (pin "1") (pinfunction "A_1") (pintype "passive"))
      (node (ref "R2") (pin "1") (pinfunction "1_1") (pintype "passive"))
    )
    (net (code "47") (name "Net-(OK1-A1)") (class "Default")
      (node (ref "OK1") (pin "4") (pinfunction "A1_4") (pintype "passive"))
      (node (ref "R12") (pin "2") (pinfunction "2_2") (pintype "passive"))
      (node (ref "T1") (pin "G") (pinfunction "G_G") (pintype "passive"))
    )
    (net (code "48") (name "Net-(OK1-A2)") (class "Default")
      (node (ref "OK1") (pin "6") (pinfunction "A2_6") (pintype "passive"))
      (node (ref "R15") (pin "2") (pinfunction "2_2") (pintype "passive"))
    )
    (net (code "49") (name "Net-(OK2-A)") (class "Default")
      (node (ref "OK2") (pin "1") (pinfunction "A_1") (pintype "passive"))
      (node (ref "R7") (pin "1") (pinfunction "1_1") (pintype "passive"))
    )
    (net (code "50") (name "Net-(OK2-A1)") (class "Default")
      (node (ref "OK2") (pin "4") (pinfunction "A1_4") (pintype "passive"))
      (node (ref "R8") (pin "2") (pinfunction "2_2") (pintype "passive"))
      (node (ref "T2") (pin "G") (pinfunction "G_G") (pintype "passive"))
    )
    (net (code "51") (name "Net-(OK2-A2)") (class "Default")
      (node (ref "OK2") (pin "6") (pinfunction "A2_6") (pintype "passive"))
      (node (ref "R9") (pin "2") (pinfunction "2_2") (pintype "passive"))
    )
    (net (code "52") (name "Net-(OK3-A)") (class "Default")
      (node (ref "OK3") (pin "1") (pinfunction "A_1") (pintype "passive"))
      (node (ref "R17") (pin "1") (pinfunction "1_1") (pintype "passive"))
    )
    (net (code "53") (name "Net-(OK3-A1)") (class "Default")
      (node (ref "OK3") (pin "4") (pinfunction "A1_4") (pintype "passive"))
      (node (ref "R18") (pin "2") (pinfunction "2_2") (pintype "passive"))
      (node (ref "T3") (pin "G") (pinfunction "G_G") (pintype "passive"))
    )
    (net (code "54") (name "Net-(OK3-A2)") (class "Default")
      (node (ref "OK3") (pin "6") (pinfunction "A2_6") (pintype "passive"))
      (node (ref "R20") (pin "2") (pinfunction "2_2") (pintype "passive"))
    )
    (net (code "55") (name "Net-(OK4-A)") (class "Default")
      (node (ref "OK4") (pin "1") (pinfunction "A_1") (pintype "passive"))
      (node (ref "R24") (pin "1") (pinfunction "1_1") (pintype "passive"))
    )
    (net (code "56") (name "Net-(OK4-A1)") (class "Default")
      (node (ref "OK4") (pin "4") (pinfunction "A1_4") (pintype "passive"))
      (node (ref "R25") (pin "2") (pinfunction "2_2") (pintype "passive"))
      (node (ref "T4") (pin "G") (pinfunction "G_G") (pintype "passive"))
    )
    (net (code "57") (name "Net-(OK4-A2)") (class "Default")
      (node (ref "OK4") (pin "6") (pinfunction "A2_6") (pintype "passive"))
      (node (ref "R26") (pin "2") (pinfunction "2_2") (pintype "passive"))
    )
    (net (code "58") (name "Net-(OK5-A)") (class "Default")
      (node (ref "OK5") (pin "1") (pinfunction "A_1") (pintype "passive"))
      (node (ref "R34") (pin "1") (pinfunction "1_1") (pintype "passive"))
    )
    (net (code "59") (name "Net-(OK5-A1)") (class "Default")
      (node (ref "OK5") (pin "4") (pinfunction "A1_4") (pintype "passive"))
      (node (ref "R36") (pin "2") (pinfunction "2_2") (pintype "passive"))
      (node (ref "T5") (pin "G") (pinfunction "G_G") (pintype "passive"))
    )
    (net (code "60") (name "Net-(OK5-A2)") (class "Default")
      (node (ref "OK5") (pin "6") (pinfunction "A2_6") (pintype "passive"))
      (node (ref "R37") (pin "2") (pinfunction "2_2") (pintype "passive"))
    )
    (net (code "61") (name "Net-(OK6-A)") (class "Default")
      (node (ref "OK6") (pin "1") (pinfunction "A_1") (pintype "passive"))
      (node (ref "R16") (pin "1") (pinfunction "1_1") (pintype "passive"))
    )
    (net (code "62") (name "Net-(OK6-A1)") (class "Default")
      (node (ref "OK6") (pin "4") (pinfunction "A1_4") (pintype "passive"))
      (node (ref "R19") (pin "2") (pinfunction "2_2") (pintype "passive"))
      (node (ref "T6") (pin "G") (pinfunction "G_G") (pintype "passive"))
    )
    (net (code "63") (name "Net-(OK6-A2)") (class "Default")
      (node (ref "OK6") (pin "6") (pinfunction "A2_6") (pintype "passive"))
      (node (ref "R21") (pin "2") (pinfunction "2_2") (pintype "passive"))
    )
    (net (code "64") (name "Net-(OK7-A)") (class "Default")
      (node (ref "OK7") (pin "1") (pinfunction "A_1") (pintype "passive"))
      (node (ref "R50") (pin "1") (pinfunction "1_1") (pintype "passive"))
    )
    (net (code "65") (name "Net-(OK7-A1)") (class "Default")
      (node (ref "OK7") (pin "4") (pinfunction "A1_4") (pintype "passive"))
      (node (ref "R51") (pin "2") (pinfunction "2_2") (pintype "passive"))
      (node (ref "T7") (pin "G") (pinfunction "G_G") (pintype "passive"))
    )
    (net (code "66") (name "Net-(OK7-A2)") (class "Default")
      (node (ref "OK7") (pin "6") (pinfunction "A2_6") (pintype "passive"))
      (node (ref "R62") (pin "2") (pinfunction "2_2") (pintype "passive"))
    )
    (net (code "67") (name "Net-(OK8-A)") (class "Default")
      (node (ref "OK8") (pin "1") (pinfunction "A_1") (pintype "passive"))
      (node (ref "R63") (pin "1") (pinfunction "1_1") (pintype "passive"))
    )
    (net (code "68") (name "Net-(OK8-A1)") (class "Default")
      (node (ref "OK8") (pin "4") (pinfunction "A1_4") (pintype "passive"))
      (node (ref "R64") (pin "2") (pinfunction "2_2") (pintype "passive"))
      (node (ref "T8") (pin "G") (pinfunction "G_G") (pintype "passive"))
    )
    (net (code "69") (name "Net-(OK8-A2)") (class "Default")
      (node (ref "OK8") (pin "6") (pinfunction "A2_6") (pintype "passive"))
      (node (ref "R65") (pin "2") (pinfunction "2_2") (pintype "passive"))
    )
    (net (code "70") (name "Net-(OK9-A)") (class "Default")
      (node (ref "OK9") (pin "1") (pinfunction "A_1") (pintype "passive"))
      (node (ref "R66") (pin "1") (pinfunction "1_1") (pintype "passive"))
    )
    (net (code "71") (name "Net-(OK9-A1)") (class "Default")
      (node (ref "OK9") (pin "4") (pinfunction "A1_4") (pintype "passive"))
      (node (ref "R67") (pin "2") (pinfunction "2_2") (pintype "passive"))
      (node (ref "T9") (pin "G") (pinfunction "G_G") (pintype "passive"))
    )
    (net (code "72") (name "Net-(OK9-A2)") (class "Default")
      (node (ref "OK9") (pin "6") (pinfunction "A2_6") (pintype "passive"))
      (node (ref "R68") (pin "2") (pinfunction "2_2") (pintype "passive"))
    )
    (net (code "73") (name "Net-(OK10-A)") (class "Default")
      (node (ref "OK10") (pin "1") (pinfunction "A_1") (pintype "passive"))
      (node (ref "R69") (pin "1") (pinfunction "1_1") (pintype "passive"))
    )
    (net (code "74") (name "Net-(OK10-A1)") (class "Default")
      (node (ref "OK10") (pin "4") (pinfunction "A1_4") (pintype "passive"))
      (node (ref "R70") (pin "2") (pinfunction "2_2") (pintype "passive"))
      (node (ref "T10") (pin "G") (pinfunction "G_G") (pintype "passive"))
    )
    (net (code "75") (name "Net-(OK10-A2)") (class "Default")
      (node (ref "OK10") (pin "6") (pinfunction "A2_6") (pintype "passive"))
      (node (ref "R71") (pin "2") (pinfunction "2_2") (pintype "passive"))
    )
    (net (code "76") (name "Net-(OK12-A)") (class "Default")
      (node (ref "OK12") (pin "1") (pinfunction "A_1") (pintype "passive"))
      (node (ref "Q1") (pin "C") (pinfunction "C_C") (pintype "passive"))
    )
    (net (code "77") (name "Net-(OK12-C)") (class "Default")
      (node (ref "B1") (pin "-") (pinfunction "-_-") (pintype "passive"))
      (node (ref "C21") (pin "2") (pinfunction "2_2") (pintype "passive"))
      (node (ref "D4") (pin "A") (pinfunction "A_A") (pintype "passive"))
      (node (ref "OK12") (pin "2") (pinfunction "C_2") (pintype "passive"))
      (node (ref "R55") (pin "1") (pinfunction "1_1") (pintype "passive"))
    )
    (net (code "78") (name "Net-(OK13-A)") (class "Default")
      (node (ref "LD1") (pin "C") (pinfunction "C_C") (pintype "passive"))
      (node (ref "OK13") (pin "1") (pinfunction "A_1") (pintype "passive"))
    )
    (net (code "79") (name "Net-(OK13-C)") (class "Default")
      (node (ref "OK13") (pin "2") (pinfunction "C_2") (pintype "passive"))
      (node (ref "R30") (pin "2") (pinfunction "2_2") (pintype "passive"))
    )
    (net (code "80") (name "Net-(OK14-A)") (class "Default")
      (node (ref "LD2") (pin "C") (pinfunction "C_C") (pintype "passive"))
      (node (ref "OK14") (pin "1") (pinfunction "A_1") (pintype "passive"))
    )
    (net (code "81") (name "Net-(OK14-C)") (class "Default")
      (node (ref "OK14") (pin "2") (pinfunction "C_2") (pintype "passive"))
      (node (ref "R33") (pin "2") (pinfunction "2_2") (pintype "passive"))
    )
    (net (code "82") (name "Net-(OK15-A)") (class "Default")
      (node (ref "LD3") (pin "C") (pinfunction "C_C") (pintype "passive"))
      (node (ref "OK15") (pin "1") (pinfunction "A_1") (pintype "passive"))
    )
    (net (code "83") (name "Net-(OK15-C)") (class "Default")
      (node (ref "OK15") (pin "2") (pinfunction "C_2") (pintype "passive"))
      (node (ref "R38") (pin "2") (pinfunction "2_2") (pintype "passive"))
    )
    (net (code "84") (name "Net-(OK16-A)") (class "Default")
      (node (ref "LD4") (pin "C") (pinfunction "C_C") (pintype "passive"))
      (node (ref "OK16") (pin "1") (pinfunction "A_1") (pintype "passive"))
    )
    (net (code "85") (name "Net-(OK16-C)") (class "Default")
      (node (ref "OK16") (pin "2") (pinfunction "C_2") (pintype "passive"))
      (node (ref "R40") (pin "2") (pinfunction "2_2") (pintype "passive"))
    )
    (net (code "86") (name "Net-(OUTS1-5A-KL)") (class "Default")
      (node (ref "OUTS1-5") (pin "1") (pinfunction "KL_1") (pintype "passive"))
      (node (ref "R20") (pin "1") (pinfunction "1_1") (pintype "passive"))
      (node (ref "R26") (pin "1") (pinfunction "1_1") (pintype "passive"))
      (node (ref "R37") (pin "1") (pinfunction "1_1") (pintype "passive"))
      (node (ref "R46") (pin "1") (pinfunction "1_1") (pintype "passive"))
      (node (ref "R9") (pin "1") (pinfunction "1_1") (pintype "passive"))
      (node (ref "T1") (pin "A2") (pinfunction "A2_A2") (pintype "passive"))
      (node (ref "T2") (pin "A2") (pinfunction "A2_A2") (pintype "passive"))
      (node (ref "T3") (pin "A2") (pinfunction "A2_A2") (pintype "passive"))
      (node (ref "T4") (pin "A2") (pinfunction "A2_A2") (pintype "passive"))
      (node (ref "T5") (pin "A2") (pinfunction "A2_A2") (pintype "passive"))
    )
    (net (code "87") (name "Net-(OUTS1-5B-KL)") (class "Default")
      (node (ref "C1") (pin "2") (pinfunction "2_2") (pintype "passive"))
      (node (ref "OUTS1-5") (pin "2") (pinfunction "KL_2") (pintype "passive"))
      (node (ref "R12") (pin "1") (pinfunction "1_1") (pintype "passive"))
      (node (ref "T1") (pin "A1") (pinfunction "A1_A1") (pintype "passive"))
    )
    (net (code "88") (name "Net-(OUTS1-5C-KL)") (class "Default")
      (node (ref "OUTS1-5") (pin "3") (pinfunction "KL_3") (pintype "passive"))
      (node (ref "R8") (pin "1") (pinfunction "1_1") (pintype "passive"))
      (node (ref "T2") (pin "A1") (pinfunction "A1_A1") (pintype "passive"))
    )
    (net (code "89") (name "Net-(OUTS1-5D-KL)") (class "Default")
      (node (ref "OUTS1-5") (pin "4") (pinfunction "KL_4") (pintype "passive"))
      (node (ref "R18") (pin "1") (pinfunction "1_1") (pintype "passive"))
      (node (ref "T3") (pin "A1") (pinfunction "A1_A1") (pintype "passive"))
    )
    (net (code "90") (name "Net-(OUTS1-5E-KL)") (class "Default")
      (node (ref "OUTS1-5") (pin "5") (pinfunction "KL_5") (pintype "passive"))
      (node (ref "R25") (pin "1") (pinfunction "1_1") (pintype "passive"))
      (node (ref "T4") (pin "A1") (pinfunction "A1_A1") (pintype "passive"))
    )
    (net (code "91") (name "Net-(OUTS1-5F-KL)") (class "Default")
      (node (ref "OUTS1-5") (pin "6") (pinfunction "KL_6") (pintype "passive"))
      (node (ref "R36") (pin "1") (pinfunction "1_1") (pintype "passive"))
      (node (ref "T5") (pin "A1") (pinfunction "A1_A1") (pintype "passive"))
    )
    (net (code "92") (name "Net-(OUTS6-10A-KL)") (class "Default")
      (node (ref "OUTS6-10") (pin "1") (pinfunction "KL_1") (pintype "passive"))
      (node (ref "R21") (pin "1") (pinfunction "1_1") (pintype "passive"))
      (node (ref "R47") (pin "2") (pinfunction "2_2") (pintype "passive"))
      (node (ref "R65") (pin "1") (pinfunction "1_1") (pintype "passive"))
      (node (ref "R68") (pin "1") (pinfunction "1_1") (pintype "passive"))
      (node (ref "R71") (pin "1") (pinfunction "1_1") (pintype "passive"))
      (node (ref "T10") (pin "A2") (pinfunction "A2_A2") (pintype "passive"))
      (node (ref "T6") (pin "A2") (pinfunction "A2_A2") (pintype "passive"))
      (node (ref "T7") (pin "A2") (pinfunction "A2_A2") (pintype "passive"))
      (node (ref "T8") (pin "A2") (pinfunction "A2_A2") (pintype "passive"))
      (node (ref "T9") (pin "A2") (pinfunction "A2_A2") (pintype "passive"))
    )
    (net (code "93") (name "Net-(OUTS6-10B-KL)") (class "Default")
      (node (ref "C2") (pin "2") (pinfunction "2_2") (pintype "passive"))
      (node (ref "OUTS6-10") (pin "2") (pinfunction "KL_2") (pintype "passive"))
      (node (ref "R51") (pin "1") (pinfunction "1_1") (pintype "passive"))
      (node (ref "T7") (pin "A1") (pinfunction "A1_A1") (pintype "passive"))
    )
    (net (code "94") (name "Net-(OUTS6-10C-KL)") (class "Default")
      (node (ref "OUTS6-10") (pin "3") (pinfunction "KL_3") (pintype "passive"))
      (node (ref "R19") (pin "1") (pinfunction "1_1") (pintype "passive"))
      (node (ref "T6") (pin "A1") (pinfunction "A1_A1") (pintype "passive"))
    )
    (net (code "95") (name "Net-(OUTS6-10D-KL)") (class "Default")
      (node (ref "OUTS6-10") (pin "4") (pinfunction "KL_4") (pintype "passive"))
      (node (ref "R64") (pin "1") (pinfunction "1_1") (pintype "passive"))
      (node (ref "T8") (pin "A1") (pinfunction "A1_A1") (pintype "passive"))
    )
    (net (code "96") (name "Net-(OUTS6-10E-KL)") (class "Default")
      (node (ref "OUTS6-10") (pin "5") (pinfunction "KL_5") (pintype "passive"))
      (node (ref "R67") (pin "1") (pinfunction "1_1") (pintype "passive"))
      (node (ref "T9") (pin "A1") (pinfunction "A1_A1") (pintype "passive"))
    )
    (net (code "97") (name "Net-(OUTS6-10F-KL)") (class "Default")
      (node (ref "OUTS6-10") (pin "6") (pinfunction "KL_6") (pintype "passive"))
      (node (ref "R70") (pin "1") (pinfunction "1_1") (pintype "passive"))
      (node (ref "T10") (pin "A1") (pinfunction "A1_A1") (pintype "passive"))
    )
    (net (code "98") (name "Net-(POWERA-KL)") (class "Default")
      (node (ref "B2") (pin "AC1") (pinfunction "AC1_AC1") (pintype "passive"))
      (node (ref "POWER") (pin "1") (pinfunction "KL_1") (pintype "passive"))
    )
    (net (code "99") (name "Net-(POWERB-KL)") (class "Default")
      (node (ref "B2") (pin "AC2") (pinfunction "AC2_AC2") (pintype "passive"))
      (node (ref "POWER") (pin "2") (pinfunction "KL_2") (pintype "passive"))
    )
    (net (code "100") (name "Net-(Q1-PadE)") (class "Default")
      (node (ref "Q1") (pin "E") (pinfunction "E_E") (pintype "passive"))
      (node (ref "R56") (pin "1") (pinfunction "1_1") (pintype "passive"))
    )
    (net (code "101") (name "Net-(R11-Pad1)") (class "Default")
      (node (ref "R11") (pin "1") (pinfunction "1_1") (pintype "passive"))
      (node (ref "R13") (pin "2") (pinfunction "2_2") (pintype "passive"))
    )
    (net (code "102") (name "Net-(R13-Pad1)") (class "Default")
      (node (ref "R13") (pin "1") (pinfunction "1_1") (pintype "passive"))
      (node (ref "R14") (pin "2") (pinfunction "2_2") (pintype "passive"))
    )
    (net (code "103") (name "Net-(R22-Pad1)") (class "Default")
      (node (ref "R22") (pin "1") (pinfunction "1_1") (pintype "passive"))
      (node (ref "R23") (pin "2") (pinfunction "2_2") (pintype "passive"))
    )
    (net (code "104") (name "Net-(R23-Pad1)") (class "Default")
      (node (ref "R23") (pin "1") (pinfunction "1_1") (pintype "passive"))
      (node (ref "R27") (pin "2") (pinfunction "2_2") (pintype "passive"))
    )
    (net (code "105") (name "Net-(R29-Pad2)") (class "Default")
      (node (ref "R29") (pin "2") (pinfunction "2_2") (pintype "passive"))
      (node (ref "R73") (pin "1") (pinfunction "1_1") (pintype "passive"))
    )
    (net (code "106") (name "Net-(R30-Pad1)") (class "Default")
      (node (ref "R30") (pin "1") (pinfunction "1_1") (pintype "passive"))
      (node (ref "R75") (pin "2") (pinfunction "2_2") (pintype "passive"))
    )
    (net (code "107") (name "Net-(R31-Pad2)") (class "Default")
      (node (ref "R31") (pin "2") (pinfunction "2_2") (pintype "passive"))
      (node (ref "R77") (pin "1") (pinfunction "1_1") (pintype "passive"))
    )
    (net (code "108") (name "Net-(R33-Pad1)") (class "Default")
      (node (ref "R33") (pin "1") (pinfunction "1_1") (pintype "passive"))
      (node (ref "R79") (pin "2") (pinfunction "2_2") (pintype "passive"))
    )
    (net (code "109") (name "Net-(R35-Pad2)") (class "Default")
      (node (ref "R35") (pin "2") (pinfunction "2_2") (pintype "passive"))
      (node (ref "R81") (pin "1") (pinfunction "1_1") (pintype "passive"))
    )
    (net (code "110") (name "Net-(R38-Pad1)") (class "Default")
      (node (ref "R38") (pin "1") (pinfunction "1_1") (pintype "passive"))
      (node (ref "R83") (pin "2") (pinfunction "2_2") (pintype "passive"))
    )
    (net (code "111") (name "Net-(R39-Pad2)") (class "Default")
      (node (ref "R39") (pin "2") (pinfunction "2_2") (pintype "passive"))
      (node (ref "R85") (pin "1") (pinfunction "1_1") (pintype "passive"))
    )
    (net (code "112") (name "Net-(R40-Pad1)") (class "Default")
      (node (ref "R40") (pin "1") (pinfunction "1_1") (pintype "passive"))
      (node (ref "R87") (pin "2") (pinfunction "2_2") (pintype "passive"))
    )
    (net (code "113") (name "Net-(R73-Pad2)") (class "Default")
      (node (ref "R73") (pin "2") (pinfunction "2_2") (pintype "passive"))
      (node (ref "R74") (pin "1") (pinfunction "1_1") (pintype "passive"))
    )
    (net (code "114") (name "Net-(R75-Pad1)") (class "Default")
      (node (ref "R75") (pin "1") (pinfunction "1_1") (pintype "passive"))
      (node (ref "R76") (pin "2") (pinfunction "2_2") (pintype "passive"))
    )
    (net (code "115") (name "Net-(R77-Pad2)") (class "Default")
      (node (ref "R77") (pin "2") (pinfunction "2_2") (pintype "passive"))
      (node (ref "R78") (pin "1") (pinfunction "1_1") (pintype "passive"))
    )
    (net (code "116") (name "Net-(R79-Pad1)") (class "Default")
      (node (ref "R79") (pin "1") (pinfunction "1_1") (pintype "passive"))
      (node (ref "R80") (pin "2") (pinfunction "2_2") (pintype "passive"))
    )
    (net (code "117") (name "Net-(R81-Pad2)") (class "Default")
      (node (ref "R81") (pin "2") (pinfunction "2_2") (pintype "passive"))
      (node (ref "R82") (pin "1") (pinfunction "1_1") (pintype "passive"))
    )
    (net (code "118") (name "Net-(R83-Pad1)") (class "Default")
      (node (ref "R83") (pin "1") (pinfunction "1_1") (pintype "passive"))
      (node (ref "R84") (pin "2") (pinfunction "2_2") (pintype "passive"))
    )
    (net (code "119") (name "Net-(R85-Pad2)") (class "Default")
      (node (ref "R85") (pin "2") (pinfunction "2_2") (pintype "passive"))
      (node (ref "R86") (pin "1") (pinfunction "1_1") (pintype "passive"))
    )
    (net (code "120") (name "Net-(R87-Pad1)") (class "Default")
      (node (ref "R87") (pin "1") (pinfunction "1_1") (pintype "passive"))
      (node (ref "R88") (pin "2") (pinfunction "2_2") (pintype "passive"))
    )
    (net (code "121") (name "Net-(U1-TXD{slash}IO1)") (class "Default")
      (node (ref "R49") (pin "1") (pinfunction "1_1") (pintype "passive"))
      (node (ref "U1") (pin "35") (pinfunction "TXD/IO1_35") (pintype "bidirectional"))
    )
    (net (code "122") (name "OUT1") (class "Default")
      (node (ref "R2") (pin "2") (pinfunction "2_2") (pintype "passive"))
      (node (ref "U1") (pin "11") (pinfunction "IO26_11") (pintype "bidirectional"))
    )
    (net (code "123") (name "OUT2") (class "Default")
      (node (ref "R7") (pin "2") (pinfunction "2_2") (pintype "passive"))
      (node (ref "U1") (pin "10") (pinfunction "IO25_10") (pintype "bidirectional"))
    )
    (net (code "124") (name "OUT3") (class "Default")
      (node (ref "R17") (pin "2") (pinfunction "2_2") (pintype "passive"))
      (node (ref "U1") (pin "36") (pinfunction "IO22_36") (pintype "bidirectional"))
    )
    (net (code "125") (name "OUT4") (class "Default")
      (node (ref "R24") (pin "2") (pinfunction "2_2") (pintype "passive"))
      (node (ref "U1") (pin "33") (pinfunction "IO21_33") (pintype "bidirectional"))
    )
    (net (code "126") (name "OUT5") (class "Default")
      (node (ref "R34") (pin "2") (pinfunction "2_2") (pintype "passive"))
      (node (ref "U1") (pin "31") (pinfunction "MISO_V/IO19_31") (pintype "bidirectional"))
    )
    (net (code "127") (name "OUT6") (class "Default")
      (node (ref "R50") (pin "2") (pinfunction "2_2") (pintype "passive"))
      (node (ref "U1") (pin "30") (pinfunction "SCK_V/IO18_30") (pintype "bidirectional"))
    )
    (net (code "128") (name "OUT7") (class "Default")
      (node (ref "R16") (pin "2") (pinfunction "2_2") (pintype "passive"))
      (node (ref "U1") (pin "29") (pinfunction "CS0_V/IO5_29") (pintype "bidirectional"))
    )
    (net (code "129") (name "OUT8") (class "Default")
      (node (ref "R63") (pin "2") (pinfunction "2_2") (pintype "passive"))
      (node (ref "U1") (pin "28") (pinfunction "IO17_28") (pintype "bidirectional"))
    )
    (net (code "130") (name "OUT9") (class "Default")
      (node (ref "R66") (pin "2") (pinfunction "2_2") (pintype "passive"))
      (node (ref "U1") (pin "27") (pinfunction "IO16_27") (pintype "bidirectional"))
    )
    (net (code "131") (name "OUT10") (class "Default")
      (node (ref "R69") (pin "2") (pinfunction "2_2") (pintype "passive"))
      (node (ref "U1") (pin "26") (pinfunction "IO4_26") (pintype "bidirectional"))
    )
    (net (code "132") (name "RX") (class "Default")
      (node (ref "DEBUG") (pin "2") (pinfunction "2_2") (pintype "passive"))
      (node (ref "IC5") (pin "8") (pinfunction "TXO_8") (pintype "bidirectional"))
      (node (ref "U1") (pin "34") (pinfunction "RXD/IO3_34") (pintype "bidirectional"))
    )
    (net (code "133") (name "TX") (class "Default")
      (node (ref "DEBUG") (pin "3") (pinfunction "3_3") (pintype "passive"))
      (node (ref "IC5") (pin "9") (pinfunction "RXI_9") (pintype "bidirectional"))
      (node (ref "R49") (pin "2") (pinfunction "2_2") (pintype "passive"))
    )
    (net (code "134") (name "USB-RST") (class "Default")
      (node (ref "C5") (pin "2") (pinfunction "2_2") (pintype "passive"))
      (node (ref "D1") (pin "A") (pinfunction "A_A") (pintype "passive"))
      (node (ref "R28") (pin "1") (pinfunction "1_1") (pintype "passive"))
      (node (ref "RESET") (pin "1") (pinfunction "1_1") (pintype "passive"))
      (node (ref "RESET") (pin "2") (pinfunction "2_2") (pintype "passive"))
    )
    (net (code "135") (name "V-USB") (class "Default")
      (node (ref "C26") (pin "1") (pinfunction "1_1") (pintype "passive"))
      (node (ref "C28") (pin "1") (pinfunction "1_1") (pintype "passive"))
      (node (ref "D2") (pin "A") (pinfunction "A_A") (pintype "passive"))
      (node (ref "IC5") (pin "7") (pinfunction "VCC_7") (pintype "bidirectional"))
      (node (ref "USB") (pin "1") (pinfunction "+5V_1") (pintype "bidirectional"))
    )
    (net (code "136") (name "unconnected-(IC5-TNOW-Pad6)") (class "Default")
      (node (ref "IC5") (pin "6") (pinfunction "TNOW_6") (pintype "bidirectional"))
    )
    (net (code "137") (name "unconnected-(IC5-~{CTS}-Pad5)") (class "Default")
      (node (ref "IC5") (pin "5") (pinfunction "~{CTS}_5") (pintype "bidirectional"))
    )
    (net (code "138") (name "unconnected-(U1-NC-Pad32)") (class "Default")
      (node (ref "U1") (pin "32") (pinfunction "NC_32") (pintype "bidirectional"))
    )
    (net (code "139") (name "unconnected-(U1-SCK{slash}IO6-Pad20)") (class "Default")
      (node (ref "U1") (pin "20") (pinfunction "SCK/IO6_20") (pintype "bidirectional"))
    )
    (net (code "140") (name "unconnected-(U1-SCS{slash}IO11-Pad19)") (class "Default")
      (node (ref "U1") (pin "19") (pinfunction "SCS/IO11_19") (pintype "bidirectional"))
    )
    (net (code "141") (name "unconnected-(U1-SDI{slash}IO8-Pad22)") (class "Default")
      (node (ref "U1") (pin "22") (pinfunction "SDI/IO8_22") (pintype "bidirectional"))
    )
    (net (code "142") (name "unconnected-(U1-SDO{slash}IO7-Pad21)") (class "Default")
      (node (ref "U1") (pin "21") (pinfunction "SDO/IO7_21") (pintype "bidirectional"))
    )
    (net (code "143") (name "unconnected-(U1-SHD{slash}IO9-Pad17)") (class "Default")
      (node (ref "U1") (pin "17") (pinfunction "SHD/IO9_17") (pintype "bidirectional"))
    )
    (net (code "144") (name "unconnected-(U1-SWP{slash}IO10-Pad18)") (class "Default")
      (node (ref "U1") (pin "18") (pinfunction "SWP/IO10_18") (pintype "bidirectional"))
    )
    (net (code "145") (name "unconnected-(USB-ID-Pad4)") (class "Default")
      (node (ref "USB") (pin "4") (pinfunction "ID_4") (pintype "bidirectional"))
    )
    (net (code "146") (name "unconnected-(X1A-KL-Pad1)") (class "Default")
      (node (ref "X1") (pin "1") (pinfunction "KL_1") (pintype "passive"))
    )
    (net (code "147") (name "unconnected-(X1B-KL-Pad2)") (class "Default")
      (node (ref "X1") (pin "2") (pinfunction "KL_2") (pintype "passive"))
    )
    (net (code "148") (name "unconnected-(X1C-KL-Pad3)") (class "Default")
      (node (ref "X1") (pin "3") (pinfunction "KL_3") (pintype "passive"))
    )
    (net (code "149") (name "unconnected-(X1D-KL-Pad4)") (class "Default")
      (node (ref "X1") (pin "4") (pinfunction "KL_4") (pintype "passive"))
    )
    (net (code "150") (name "unconnected-(X1E-KL-Pad5)") (class "Default")
      (node (ref "X1") (pin "5") (pinfunction "KL_5") (pintype "passive"))
    )
    (net (code "151") (name "unconnected-(X1F-KL-Pad6)") (class "Default")
      (node (ref "X1") (pin "6") (pinfunction "KL_6") (pintype "passive"))
    )
  )
)
